# UAA180-VU-Meter-single.net
KiCad netlist of a schematic drawn in EAGLE
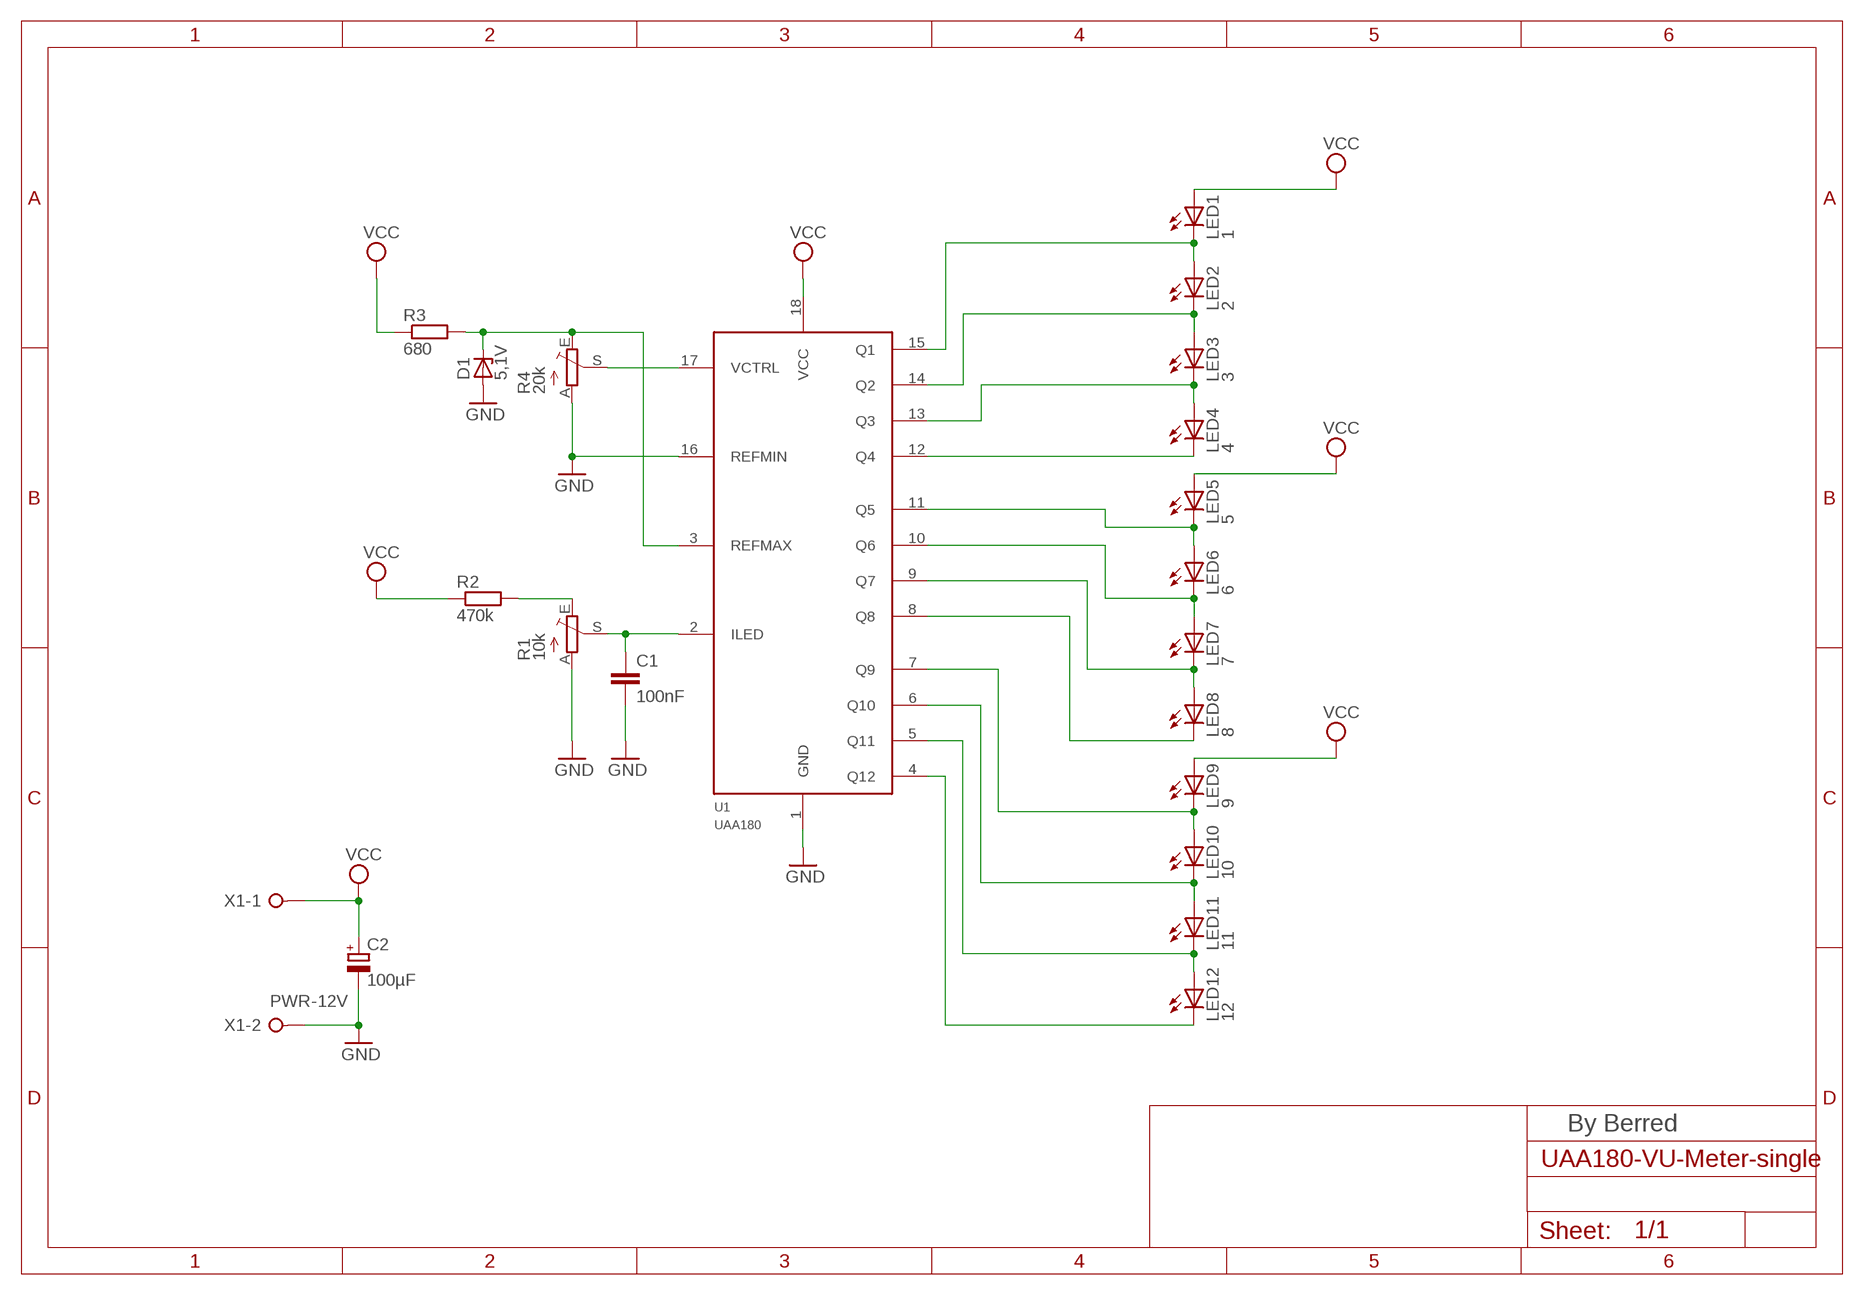
[diagram p0: schematic, sheet 1]

(export (version "E")
  (design (tool "Eeschema 10.0.6"))
  (components
    (comp (ref "C1")
      (value "100nF")
      (footprint "eagle-import:C025-024X044")
      (libsource (lib "eagle-import") (part "C-EU025-024X044"))
    )
    (comp (ref "C2")
      (value "100µF")
      (footprint "eagle-import:E2,5-7")
      (libsource (lib "eagle-import") (part "CPOL-EUE2.5-7"))
    )
    (comp (ref "D1")
      (value "5,1V")
      (footprint "eagle-import:DO35Z10")
      (libsource (lib "eagle-import") (part "ZPD"))
    )
    (comp (ref "LED1")
      (value "1")
      (footprint "eagle-import:LED2X5")
      (libsource (lib "eagle-import") (part "LEDSQR2X5"))
    )
    (comp (ref "LED2")
      (value "2")
      (footprint "eagle-import:LED2X5")
      (libsource (lib "eagle-import") (part "LEDSQR2X5"))
    )
    (comp (ref "LED3")
      (value "3")
      (footprint "eagle-import:LED2X5")
      (libsource (lib "eagle-import") (part "LEDSQR2X5"))
    )
    (comp (ref "LED4")
      (value "4")
      (footprint "eagle-import:LED2X5")
      (libsource (lib "eagle-import") (part "LEDSQR2X5"))
    )
    (comp (ref "LED5")
      (value "5")
      (footprint "eagle-import:LED2X5")
      (libsource (lib "eagle-import") (part "LEDSQR2X5"))
    )
    (comp (ref "LED6")
      (value "6")
      (footprint "eagle-import:LED2X5")
      (libsource (lib "eagle-import") (part "LEDSQR2X5"))
    )
    (comp (ref "LED7")
      (value "7")
      (footprint "eagle-import:LED2X5")
      (libsource (lib "eagle-import") (part "LEDSQR2X5"))
    )
    (comp (ref "LED8")
      (value "8")
      (footprint "eagle-import:LED2X5")
      (libsource (lib "eagle-import") (part "LEDSQR2X5"))
    )
    (comp (ref "LED9")
      (value "9")
      (footprint "eagle-import:LED2X5")
      (libsource (lib "eagle-import") (part "LEDSQR2X5"))
    )
    (comp (ref "LED10")
      (value "10")
      (footprint "eagle-import:LED2X5")
      (libsource (lib "eagle-import") (part "LEDSQR2X5"))
    )
    (comp (ref "LED11")
      (value "11")
      (footprint "eagle-import:LED2X5")
      (libsource (lib "eagle-import") (part "LEDSQR2X5"))
    )
    (comp (ref "LED12")
      (value "12")
      (footprint "eagle-import:LED2X5")
      (libsource (lib "eagle-import") (part "LEDSQR2X5"))
    )
    (comp (ref "R1")
      (value "10k")
      (footprint "eagle-import:B25P")
      (libsource (lib "eagle-import") (part "TRIM_EU-B25P"))
    )
    (comp (ref "R2")
      (value "470k")
      (footprint "eagle-import:0207_10")
      (libsource (lib "eagle-import") (part "R-EU_0207/10"))
    )
    (comp (ref "R3")
      (value "680")
      (footprint "eagle-import:0207_10")
      (libsource (lib "eagle-import") (part "R-EU_0207/10"))
    )
    (comp (ref "R4")
      (value "20k")
      (footprint "eagle-import:B25P")
      (libsource (lib "eagle-import") (part "TRIM_EU-B25P"))
    )
    (comp (ref "U1")
      (value "UAA180")
      (footprint "eagle-import:DIL18")
      (libsource (lib "eagle-import") (part "UAA180"))
    )
    (comp (ref "X1")
      (value "PWR-12V")
      (footprint "eagle-import:W237-132")
      (libsource (lib "eagle-import") (part "W237-02P"))
    )
  )
  (nets
    (net (code "1") (name "GND") (class "Default")
      (node (ref "C1") (pin "2") (pinfunction "2_2") (pintype "passive"))
      (node (ref "C2") (pin "-") (pinfunction "-_-") (pintype "passive"))
      (node (ref "D1") (pin "A") (pinfunction "A_A") (pintype "passive"))
      (node (ref "R1") (pin "A") (pinfunction "A_A") (pintype "passive"))
      (node (ref "R4") (pin "A") (pinfunction "A_A") (pintype "passive"))
      (node (ref "U1") (pin "1") (pinfunction "GND_1") (pintype "bidirectional"))
      (node (ref "U1") (pin "16") (pinfunction "REFMIN_16") (pintype "bidirectional"))
      (node (ref "X1") (pin "2") (pinfunction "KL_2") (pintype "passive"))
    )
    (net (code "2") (name "Net-(LED1-C)") (class "Default")
      (node (ref "LED1") (pin "K") (pinfunction "C_K") (pintype "passive"))
      (node (ref "LED2") (pin "A") (pinfunction "A_A") (pintype "passive"))
      (node (ref "U1") (pin "15") (pinfunction "Q1_15") (pintype "bidirectional"))
    )
    (net (code "3") (name "Net-(LED2-C)") (class "Default")
      (node (ref "LED2") (pin "K") (pinfunction "C_K") (pintype "passive"))
      (node (ref "LED3") (pin "A") (pinfunction "A_A") (pintype "passive"))
      (node (ref "U1") (pin "14") (pinfunction "Q2_14") (pintype "bidirectional"))
    )
    (net (code "4") (name "Net-(LED3-C)") (class "Default")
      (node (ref "LED3") (pin "K") (pinfunction "C_K") (pintype "passive"))
      (node (ref "LED4") (pin "A") (pinfunction "A_A") (pintype "passive"))
      (node (ref "U1") (pin "13") (pinfunction "Q3_13") (pintype "bidirectional"))
    )
    (net (code "5") (name "Net-(LED4-C)") (class "Default")
      (node (ref "LED4") (pin "K") (pinfunction "C_K") (pintype "passive"))
      (node (ref "U1") (pin "12") (pinfunction "Q4_12") (pintype "bidirectional"))
    )
    (net (code "6") (name "Net-(LED5-C)") (class "Default")
      (node (ref "LED5") (pin "K") (pinfunction "C_K") (pintype "passive"))
      (node (ref "LED6") (pin "A") (pinfunction "A_A") (pintype "passive"))
      (node (ref "U1") (pin "11") (pinfunction "Q5_11") (pintype "bidirectional"))
    )
    (net (code "7") (name "Net-(LED6-C)") (class "Default")
      (node (ref "LED6") (pin "K") (pinfunction "C_K") (pintype "passive"))
      (node (ref "LED7") (pin "A") (pinfunction "A_A") (pintype "passive"))
      (node (ref "U1") (pin "10") (pinfunction "Q6_10") (pintype "bidirectional"))
    )
    (net (code "8") (name "Net-(LED7-C)") (class "Default")
      (node (ref "LED7") (pin "K") (pinfunction "C_K") (pintype "passive"))
      (node (ref "LED8") (pin "A") (pinfunction "A_A") (pintype "passive"))
      (node (ref "U1") (pin "9") (pinfunction "Q7_9") (pintype "bidirectional"))
    )
    (net (code "9") (name "Net-(LED8-C)") (class "Default")
      (node (ref "LED8") (pin "K") (pinfunction "C_K") (pintype "passive"))
      (node (ref "U1") (pin "8") (pinfunction "Q8_8") (pintype "bidirectional"))
    )
    (net (code "10") (name "Net-(LED9-C)") (class "Default")
      (node (ref "LED10") (pin "A") (pinfunction "A_A") (pintype "passive"))
      (node (ref "LED9") (pin "K") (pinfunction "C_K") (pintype "passive"))
      (node (ref "U1") (pin "7") (pinfunction "Q9_7") (pintype "bidirectional"))
    )
    (net (code "11") (name "Net-(LED10-C)") (class "Default")
      (node (ref "LED10") (pin "K") (pinfunction "C_K") (pintype "passive"))
      (node (ref "LED11") (pin "A") (pinfunction "A_A") (pintype "passive"))
      (node (ref "U1") (pin "6") (pinfunction "Q10_6") (pintype "bidirectional"))
    )
    (net (code "12") (name "Net-(LED11-C)") (class "Default")
      (node (ref "LED11") (pin "K") (pinfunction "C_K") (pintype "passive"))
      (node (ref "LED12") (pin "A") (pinfunction "A_A") (pintype "passive"))
      (node (ref "U1") (pin "5") (pinfunction "Q11_5") (pintype "bidirectional"))
    )
    (net (code "13") (name "Net-(LED12-C)") (class "Default")
      (node (ref "LED12") (pin "K") (pinfunction "C_K") (pintype "passive"))
      (node (ref "U1") (pin "4") (pinfunction "Q12_4") (pintype "bidirectional"))
    )
    (net (code "14") (name "Net-(R1-PadE)") (class "Default")
      (node (ref "R1") (pin "E") (pinfunction "E_E") (pintype "passive"))
      (node (ref "R2") (pin "2") (pinfunction "2_2") (pintype "passive"))
    )
    (net (code "15") (name "Net-(U1-ILED)") (class "Default")
      (node (ref "C1") (pin "1") (pinfunction "1_1") (pintype "passive"))
      (node (ref "R1") (pin "S") (pinfunction "S_S") (pintype "passive"))
      (node (ref "U1") (pin "2") (pinfunction "ILED_2") (pintype "bidirectional"))
    )
    (net (code "16") (name "Net-(U1-REFMAX)") (class "Default")
      (node (ref "D1") (pin "C") (pinfunction "C_C") (pintype "passive"))
      (node (ref "R3") (pin "2") (pinfunction "2_2") (pintype "passive"))
      (node (ref "R4") (pin "E") (pinfunction "E_E") (pintype "passive"))
      (node (ref "U1") (pin "3") (pinfunction "REFMAX_3") (pintype "bidirectional"))
    )
    (net (code "17") (name "Net-(U1-VCTRL)") (class "Default")
      (node (ref "R4") (pin "S") (pinfunction "S_S") (pintype "passive"))
      (node (ref "U1") (pin "17") (pinfunction "VCTRL_17") (pintype "bidirectional"))
    )
    (net (code "18") (name "VCC") (class "Default")
      (node (ref "C2") (pin "+") (pinfunction "+_+") (pintype "passive"))
      (node (ref "LED1") (pin "A") (pinfunction "A_A") (pintype "passive"))
      (node (ref "LED5") (pin "A") (pinfunction "A_A") (pintype "passive"))
      (node (ref "LED9") (pin "A") (pinfunction "A_A") (pintype "passive"))
      (node (ref "R2") (pin "1") (pinfunction "1_1") (pintype "passive"))
      (node (ref "R3") (pin "1") (pinfunction "1_1") (pintype "passive"))
      (node (ref "U1") (pin "18") (pinfunction "VCC_18") (pintype "bidirectional"))
      (node (ref "X1") (pin "1") (pinfunction "KL_1") (pintype "passive"))
    )
  )
)
